# MatrixLED_8x8_1_9S_Sch.net
KiCad netlist of a schematic drawn in Altium Designer
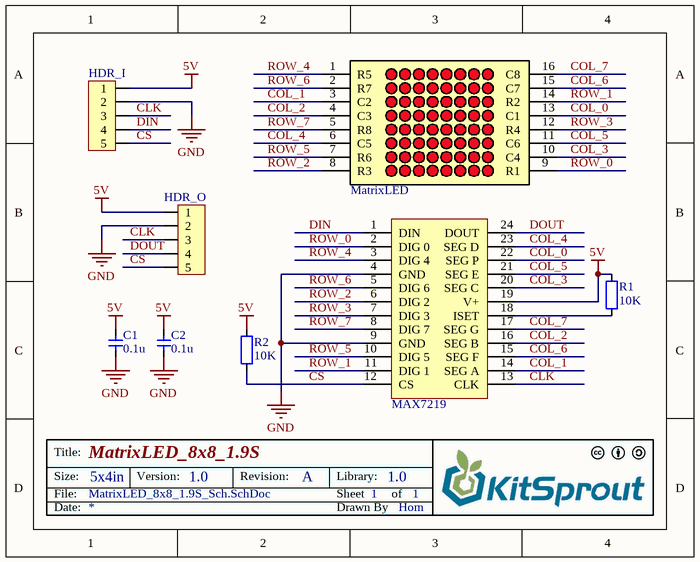
[diagram p0: MatrixLED_8x8_1.9S_Sch.SchDoc]

(export (version "E")
  (design (tool "Eeschema 10.0.6"))
  (components
    (comp (ref "C1")
      (value "0.1u")
      (footprint "PCB_PassiveCap:CAP_0603")
      (description "Capacitor")
      (fields (field (name "Comment") "Cap_0603"))
      (libsource (lib "SCH_Passive") (part "Cap_0603"))
    )
    (comp (ref "C2")
      (value "0.1u")
      (footprint "PCB_PassiveCap:CAP_0603")
      (description "Capacitor")
      (fields (field (name "Comment") "Cap_0603"))
      (libsource (lib "SCH_Passive") (part "Cap_0603"))
    )
    (comp (ref "HDR_I")
      (value "HDR1x5_2.54")
      (footprint "PCB_ConnectorHDR:HDR1X5_2.54_180")
      (description "Header")
      (libsource (lib "SCH_ConnectorHDR") (part "HDR1x5_2.54T"))
    )
    (comp (ref "HDR_O")
      (value "HDR1x5_2.54")
      (footprint "PCB_ConnectorHDR:HDR1X5_2.54_180")
      (description "Header")
      (libsource (lib "SCH_ConnectorHDR") (part "HDR1x5_2.54"))
    )
    (comp (ref "MatrixLED")
      (value "LED_Matrix_8x8_1.9S")
      (footprint "PCB_ActiveLED:LED_Matrix_8x8_1.9S")
      (description "MatrixLED")
      (libsource (lib "SCH_Active") (part "LED_Matrix_8x8_1.9S"))
    )
    (comp (ref "MAX7219")
      (value "MAX7219/21")
      (footprint "PCB_IntegratedCircuit:SOIC_E300_24")
      (description "Drivers")
      (libsource (lib "SCH_IntegratedCircuit") (part "MAX7219/21"))
    )
    (comp (ref "R1")
      (value "10K")
      (footprint "PCB_PassiveRes:RES_0603")
      (description "Resistor")
      (fields (field (name "Comment") "Res_0603"))
      (libsource (lib "SCH_Passive") (part "Res_0603"))
    )
    (comp (ref "R2")
      (value "10K")
      (footprint "PCB_PassiveRes:RES_0603")
      (description "Resistor")
      (fields (field (name "Comment") "Res_0603"))
      (libsource (lib "SCH_Passive") (part "Res_0603"))
    )
  )
  (nets
    (net (code "1") (name "/CLK") (class "Default")
      (node (ref "HDR_I") (pin "3") (pinfunction "3_3") (pintype "passive"))
      (node (ref "HDR_O") (pin "3") (pinfunction "3_3") (pintype "passive"))
      (node (ref "MAX7219") (pin "13") (pinfunction "CLK_13") (pintype "passive"))
    )
    (net (code "2") (name "/COL_0") (class "Default")
      (node (ref "MAX7219") (pin "22") (pinfunction "SEG_P_22") (pintype "passive"))
      (node (ref "MatrixLED") (pin "13") (pinfunction "C1_13") (pintype "passive"))
    )
    (net (code "3") (name "/COL_1") (class "Default")
      (node (ref "MAX7219") (pin "14") (pinfunction "SEG_A_14") (pintype "passive"))
      (node (ref "MatrixLED") (pin "3") (pinfunction "C2_3") (pintype "passive"))
    )
    (net (code "4") (name "/COL_2") (class "Default")
      (node (ref "MAX7219") (pin "16") (pinfunction "SEG_B_16") (pintype "passive"))
      (node (ref "MatrixLED") (pin "4") (pinfunction "C3_4") (pintype "passive"))
    )
    (net (code "5") (name "/COL_3") (class "Default")
      (node (ref "MAX7219") (pin "20") (pinfunction "SEG_C_20") (pintype "passive"))
      (node (ref "MatrixLED") (pin "10") (pinfunction "C4_10") (pintype "passive"))
    )
    (net (code "6") (name "/COL_4") (class "Default")
      (node (ref "MAX7219") (pin "23") (pinfunction "SEG_D_23") (pintype "passive"))
      (node (ref "MatrixLED") (pin "6") (pinfunction "C5_6") (pintype "passive"))
    )
    (net (code "7") (name "/COL_5") (class "Default")
      (node (ref "MAX7219") (pin "21") (pinfunction "SEG_E_21") (pintype "passive"))
      (node (ref "MatrixLED") (pin "11") (pinfunction "C6_11") (pintype "passive"))
    )
    (net (code "8") (name "/COL_6") (class "Default")
      (node (ref "MAX7219") (pin "15") (pinfunction "SEG_F_15") (pintype "passive"))
      (node (ref "MatrixLED") (pin "15") (pinfunction "C7_15") (pintype "passive"))
    )
    (net (code "9") (name "/COL_7") (class "Default")
      (node (ref "MAX7219") (pin "17") (pinfunction "SEG_G_17") (pintype "passive"))
      (node (ref "MatrixLED") (pin "16") (pinfunction "C8_16") (pintype "passive"))
    )
    (net (code "10") (name "/CS") (class "Default")
      (node (ref "HDR_I") (pin "5") (pinfunction "5_5") (pintype "passive"))
      (node (ref "HDR_O") (pin "5") (pinfunction "5_5") (pintype "passive"))
      (node (ref "MAX7219") (pin "12") (pinfunction "CS_12") (pintype "passive"))
      (node (ref "R2") (pin "1") (pinfunction "1_1") (pintype "passive"))
    )
    (net (code "11") (name "/DIN") (class "Default")
      (node (ref "HDR_I") (pin "4") (pinfunction "4_4") (pintype "passive"))
      (node (ref "MAX7219") (pin "1") (pinfunction "DIN_1") (pintype "passive"))
    )
    (net (code "12") (name "/DOUT") (class "Default")
      (node (ref "HDR_O") (pin "4") (pinfunction "4_4") (pintype "passive"))
      (node (ref "MAX7219") (pin "24") (pinfunction "DOUT_24") (pintype "passive"))
    )
    (net (code "13") (name "/ROW_0") (class "Default")
      (node (ref "MAX7219") (pin "2") (pinfunction "DIG_0_2") (pintype "passive"))
      (node (ref "MatrixLED") (pin "9") (pinfunction "R1_9") (pintype "passive"))
    )
    (net (code "14") (name "/ROW_1") (class "Default")
      (node (ref "MAX7219") (pin "11") (pinfunction "DIG_1_11") (pintype "passive"))
      (node (ref "MatrixLED") (pin "14") (pinfunction "R2_14") (pintype "passive"))
    )
    (net (code "15") (name "/ROW_2") (class "Default")
      (node (ref "MAX7219") (pin "6") (pinfunction "DIG_2_6") (pintype "passive"))
      (node (ref "MatrixLED") (pin "8") (pinfunction "R3_8") (pintype "passive"))
    )
    (net (code "16") (name "/ROW_3") (class "Default")
      (node (ref "MAX7219") (pin "7") (pinfunction "DIG_3_7") (pintype "passive"))
      (node (ref "MatrixLED") (pin "12") (pinfunction "R4_12") (pintype "passive"))
    )
    (net (code "17") (name "/ROW_4") (class "Default")
      (node (ref "MAX7219") (pin "3") (pinfunction "DIG_4_3") (pintype "passive"))
      (node (ref "MatrixLED") (pin "1") (pinfunction "R5_1") (pintype "passive"))
    )
    (net (code "18") (name "/ROW_5") (class "Default")
      (node (ref "MAX7219") (pin "10") (pinfunction "DIG_5_10") (pintype "passive"))
      (node (ref "MatrixLED") (pin "7") (pinfunction "R6_7") (pintype "passive"))
    )
    (net (code "19") (name "/ROW_6") (class "Default")
      (node (ref "MAX7219") (pin "5") (pinfunction "DIG_6_5") (pintype "passive"))
      (node (ref "MatrixLED") (pin "2") (pinfunction "R7_2") (pintype "passive"))
    )
    (net (code "20") (name "/ROW_7") (class "Default")
      (node (ref "MAX7219") (pin "8") (pinfunction "DIG_7_8") (pintype "passive"))
      (node (ref "MatrixLED") (pin "5") (pinfunction "R8_5") (pintype "passive"))
    )
    (net (code "21") (name "5V") (class "Default")
      (node (ref "C1") (pin "2") (pinfunction "2_2") (pintype "passive"))
      (node (ref "C2") (pin "2") (pinfunction "2_2") (pintype "passive"))
      (node (ref "HDR_I") (pin "1") (pinfunction "1_1") (pintype "passive"))
      (node (ref "HDR_O") (pin "1") (pinfunction "1_1") (pintype "passive"))
      (node (ref "MAX7219") (pin "19") (pinfunction "V+_19") (pintype "passive"))
      (node (ref "R1") (pin "2") (pinfunction "2_2") (pintype "passive"))
      (node (ref "R2") (pin "2") (pinfunction "2_2") (pintype "passive"))
    )
    (net (code "22") (name "GND") (class "Default")
      (node (ref "C1") (pin "1") (pinfunction "1_1") (pintype "passive"))
      (node (ref "C2") (pin "1") (pinfunction "1_1") (pintype "passive"))
      (node (ref "HDR_I") (pin "2") (pinfunction "2_2") (pintype "passive"))
      (node (ref "HDR_O") (pin "2") (pinfunction "2_2") (pintype "passive"))
      (node (ref "MAX7219") (pin "4") (pinfunction "GND_4") (pintype "passive"))
      (node (ref "MAX7219") (pin "9") (pinfunction "GND_9") (pintype "passive"))
    )
    (net (code "23") (name "Net-(MAX7219-ISET)") (class "Default")
      (node (ref "MAX7219") (pin "18") (pinfunction "ISET_18") (pintype "passive"))
      (node (ref "R1") (pin "1") (pinfunction "1_1") (pintype "passive"))
    )
  )
)
